# PSPS_AVNC_SRD_sensors-2020-10-12.net
KiCad netlist of a schematic drawn in EAGLE
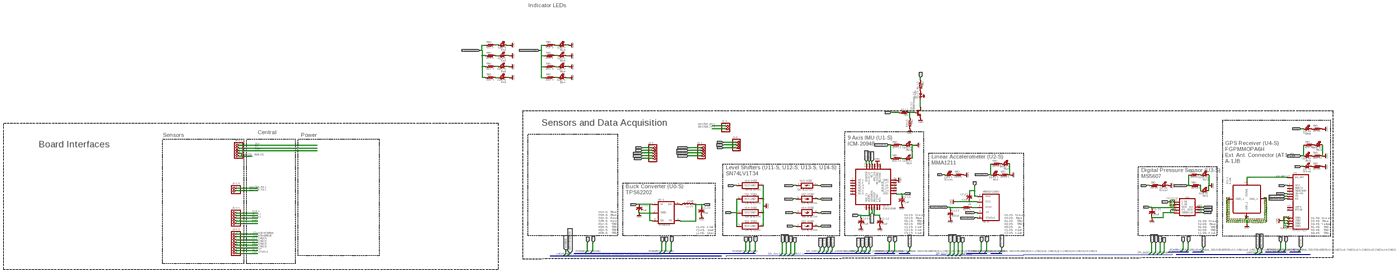
[diagram p0: schematic, sheet 1, overview]
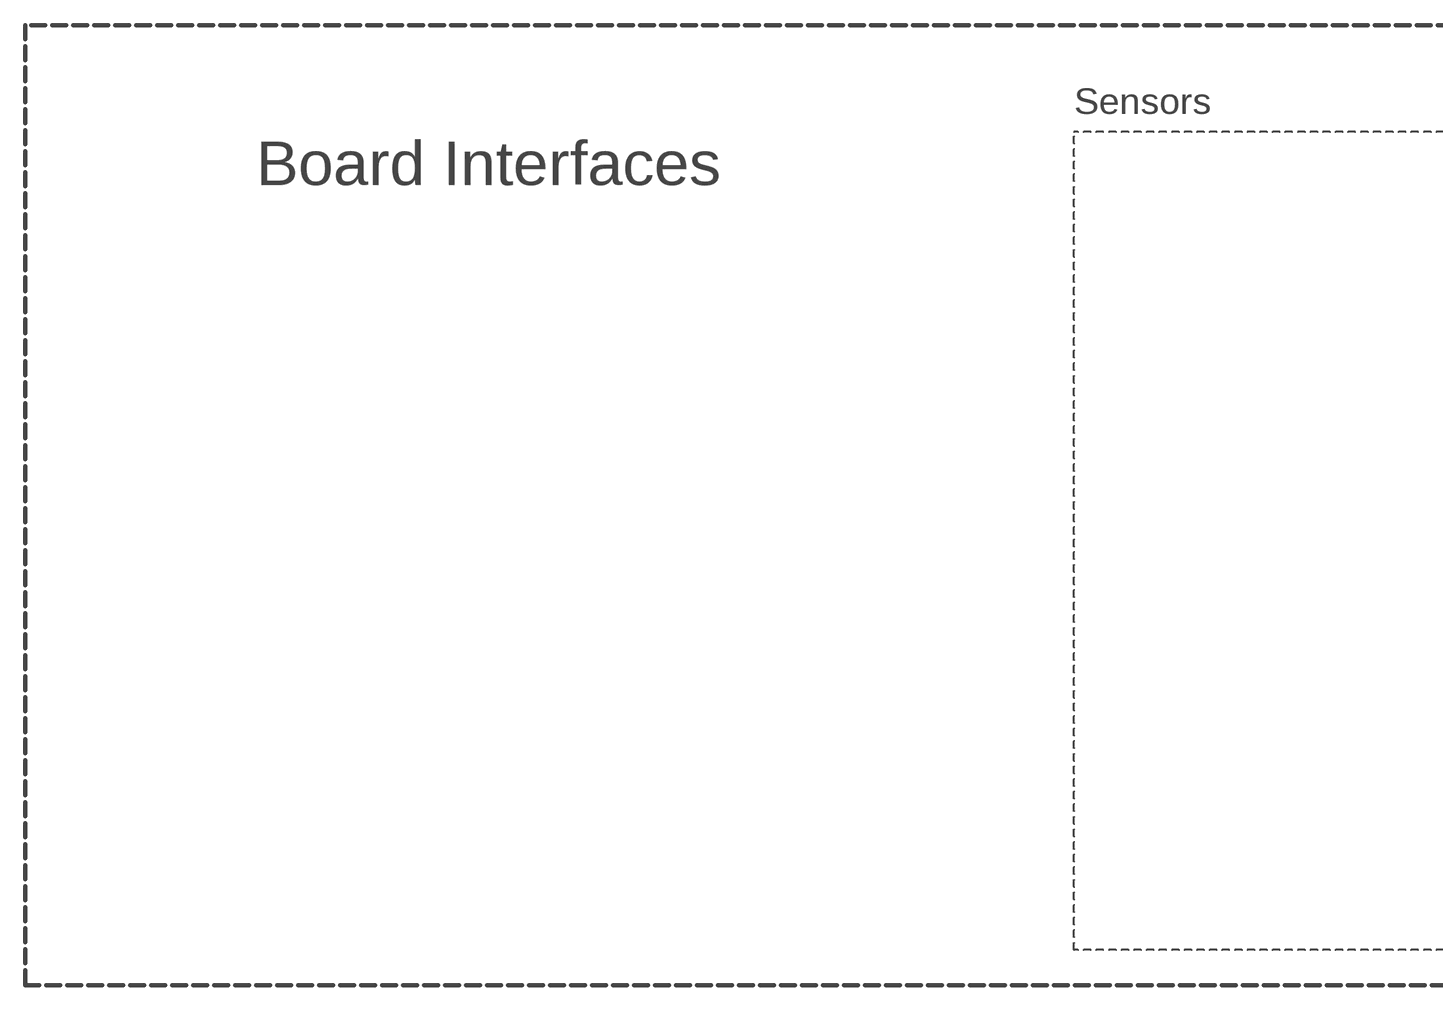
[diagram p1: schematic, sheet 1, part 1 of 4]
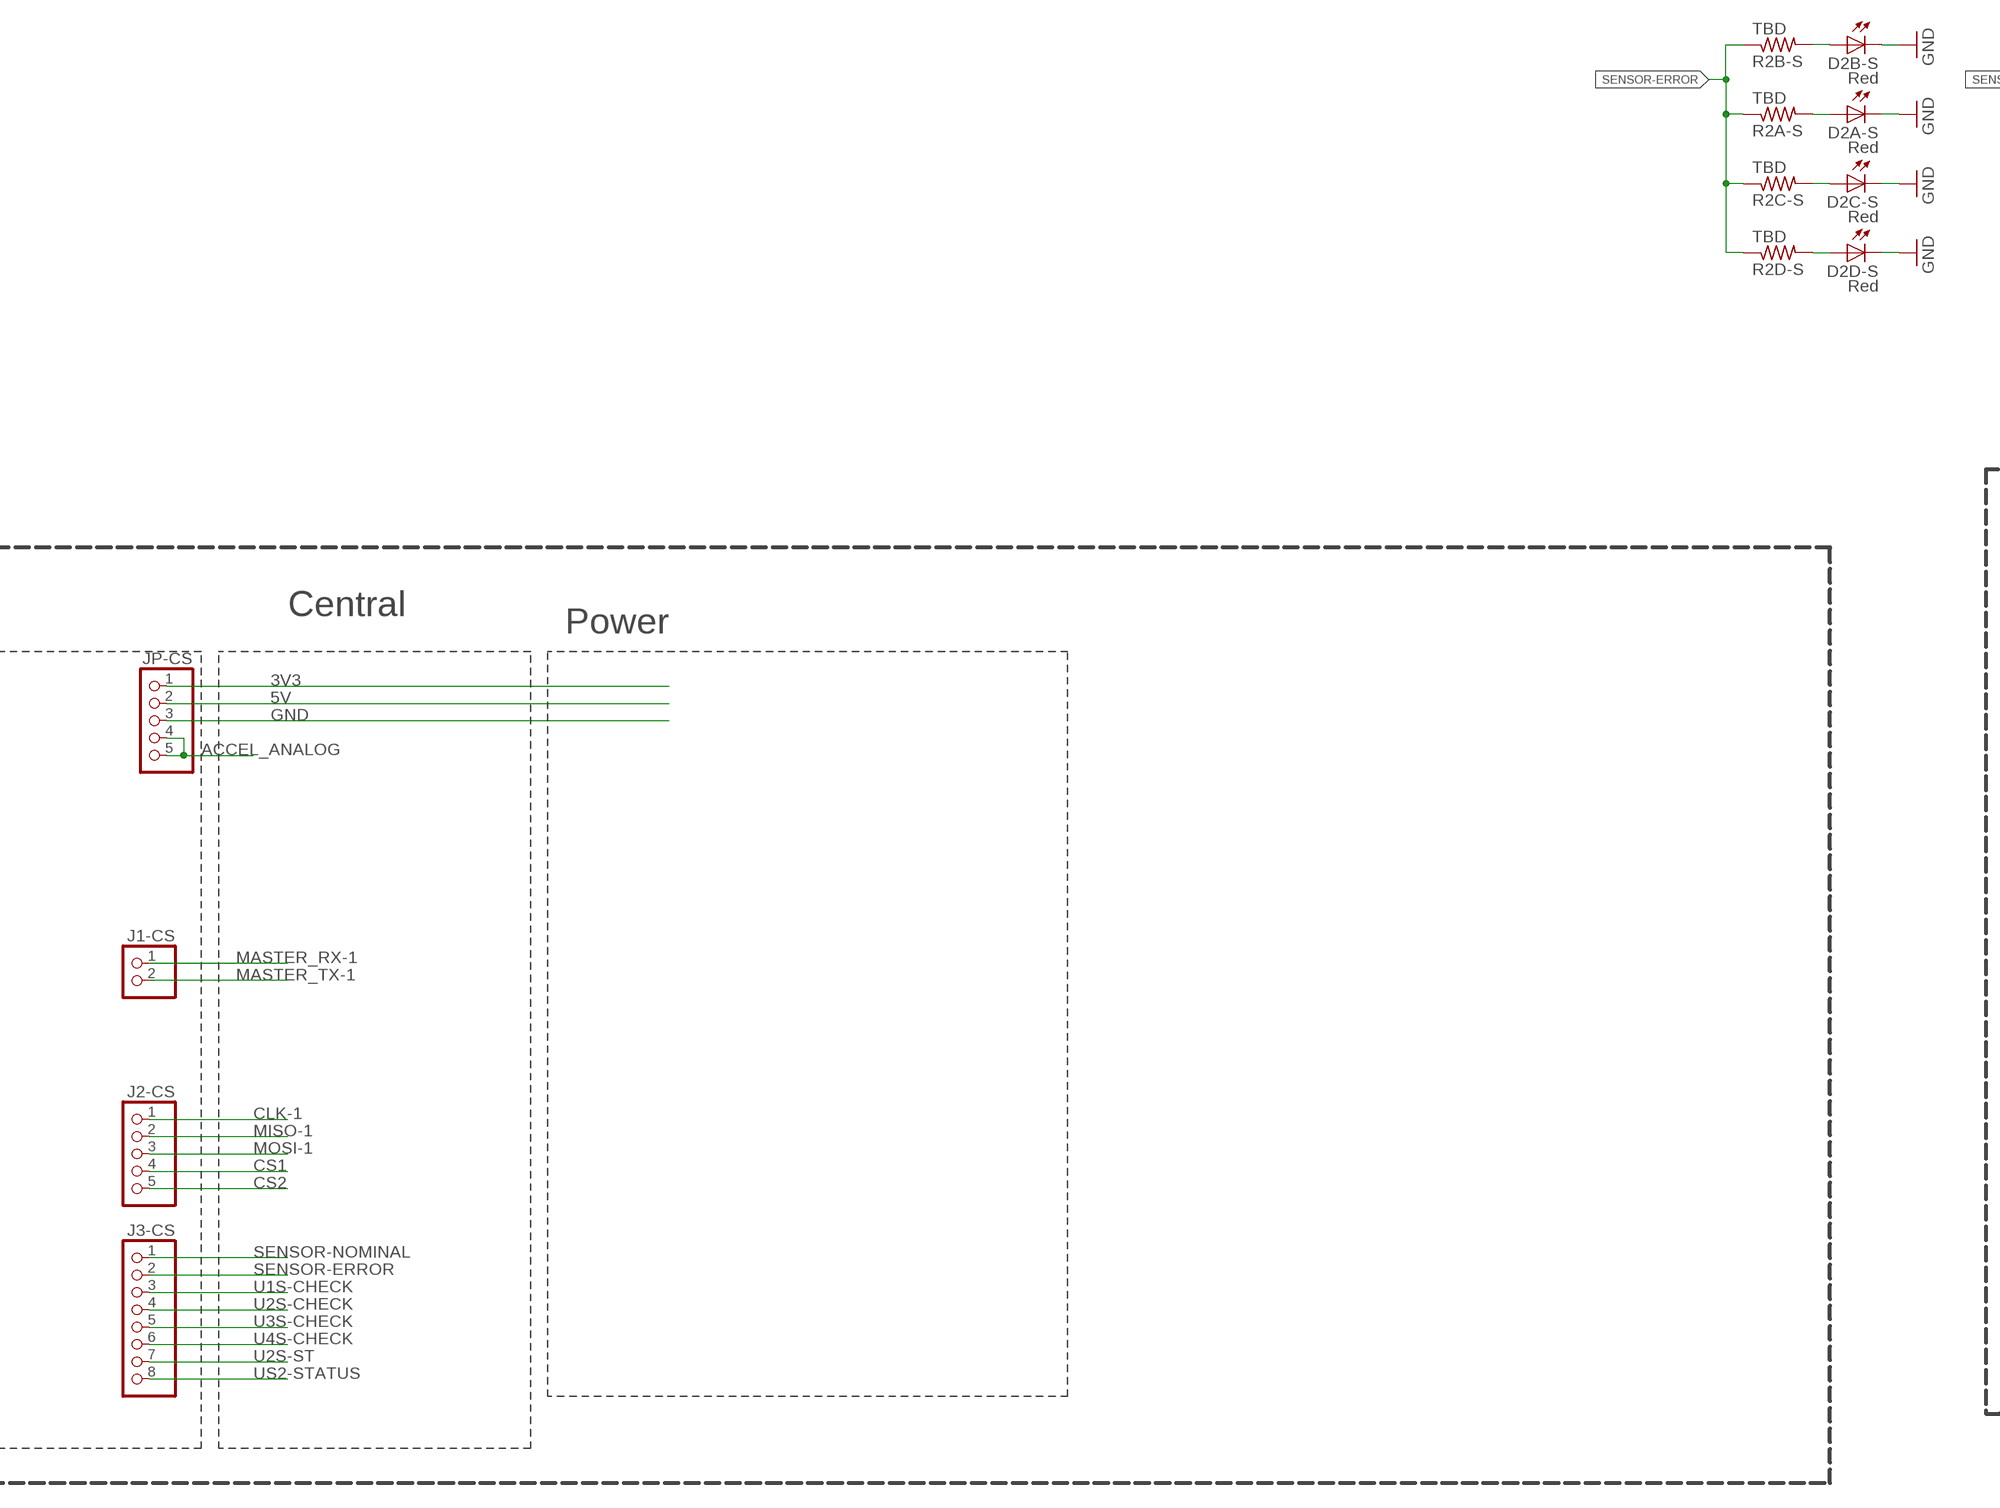
[diagram p2: schematic, sheet 1, part 2 of 4]
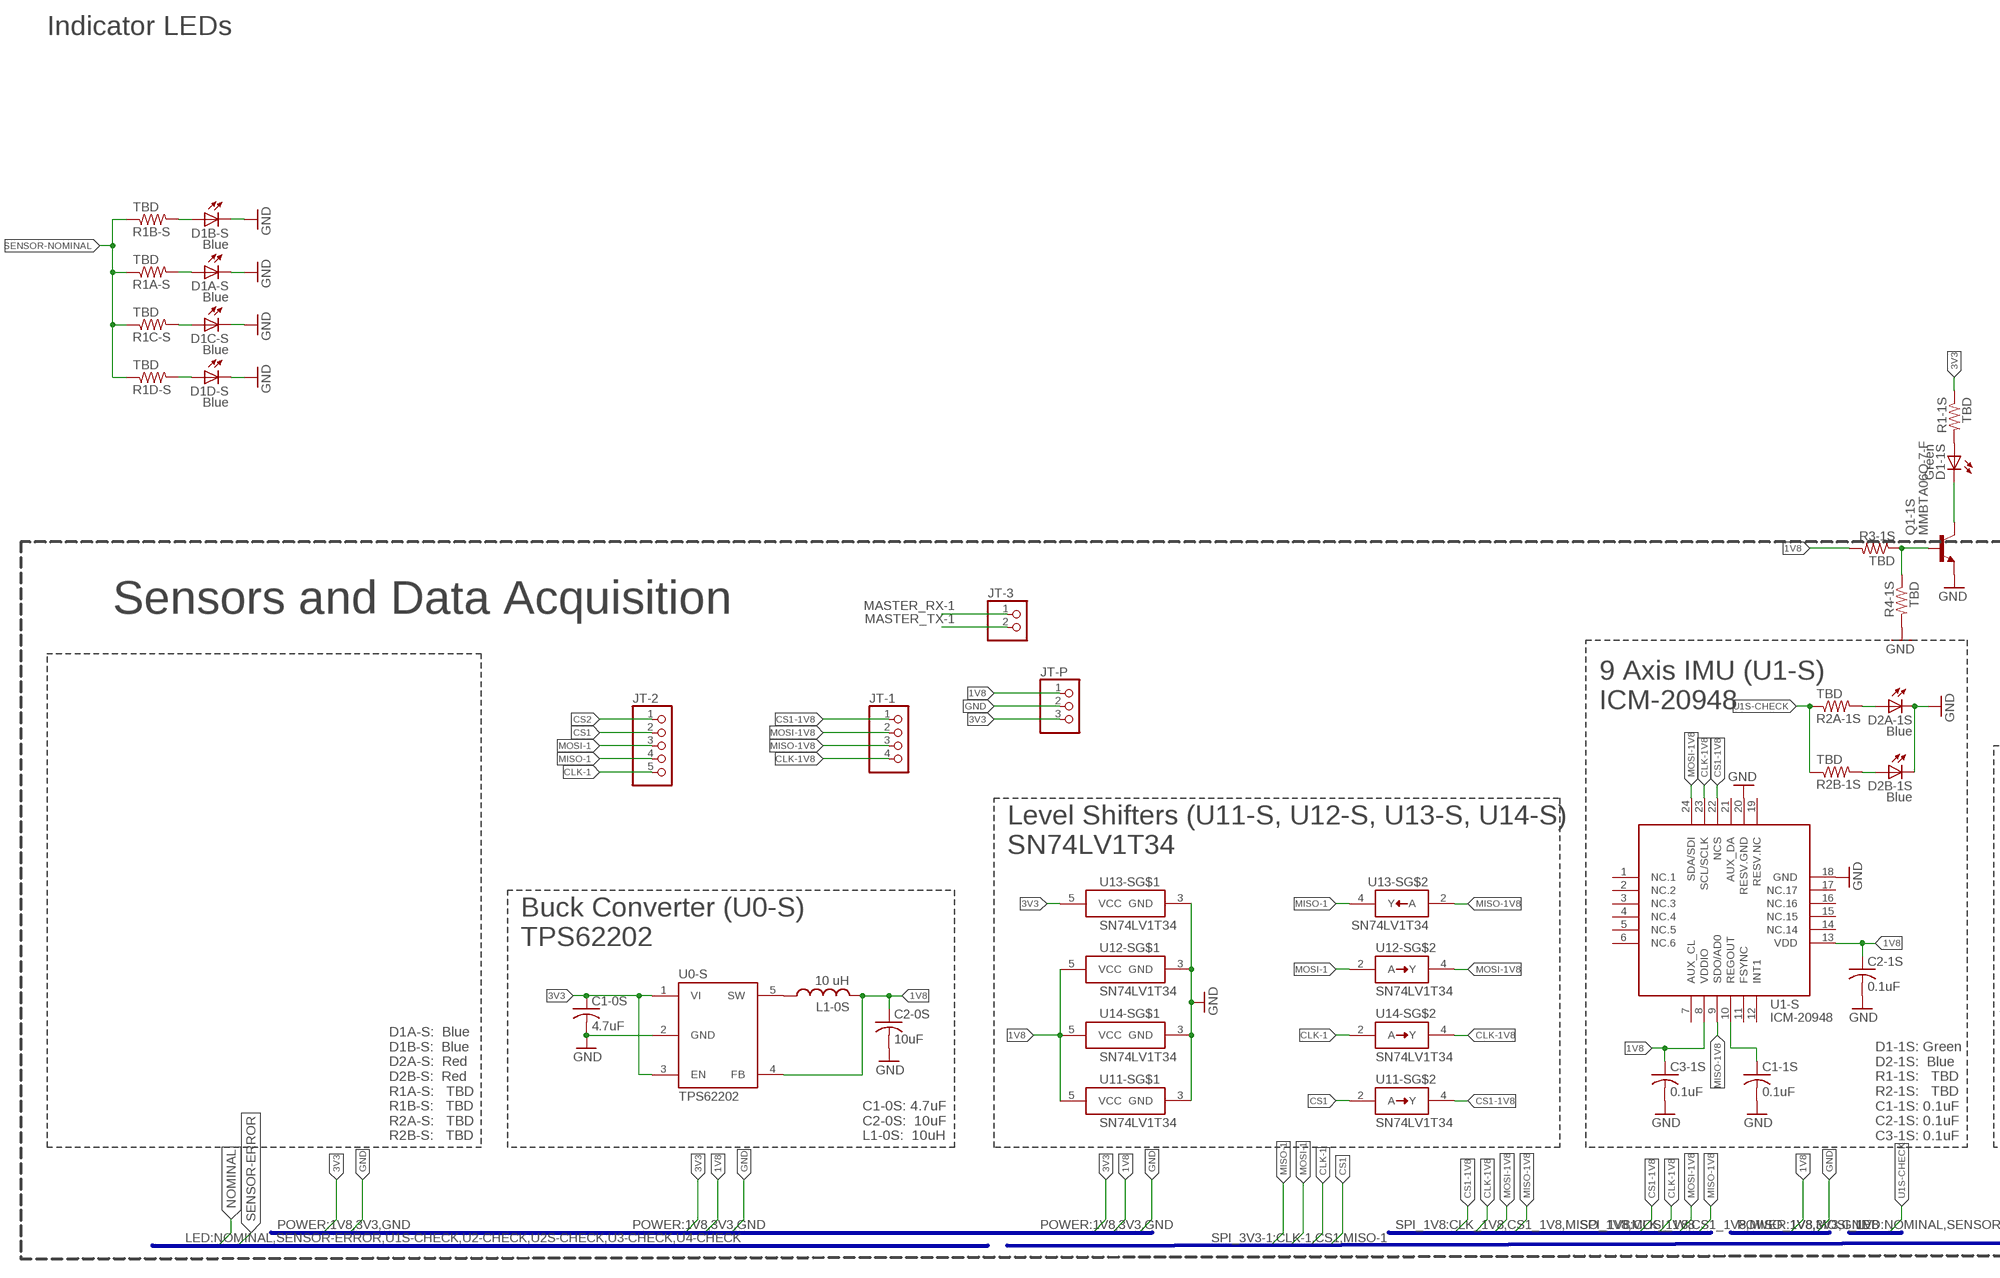
[diagram p3: schematic, sheet 1, part 3 of 4]
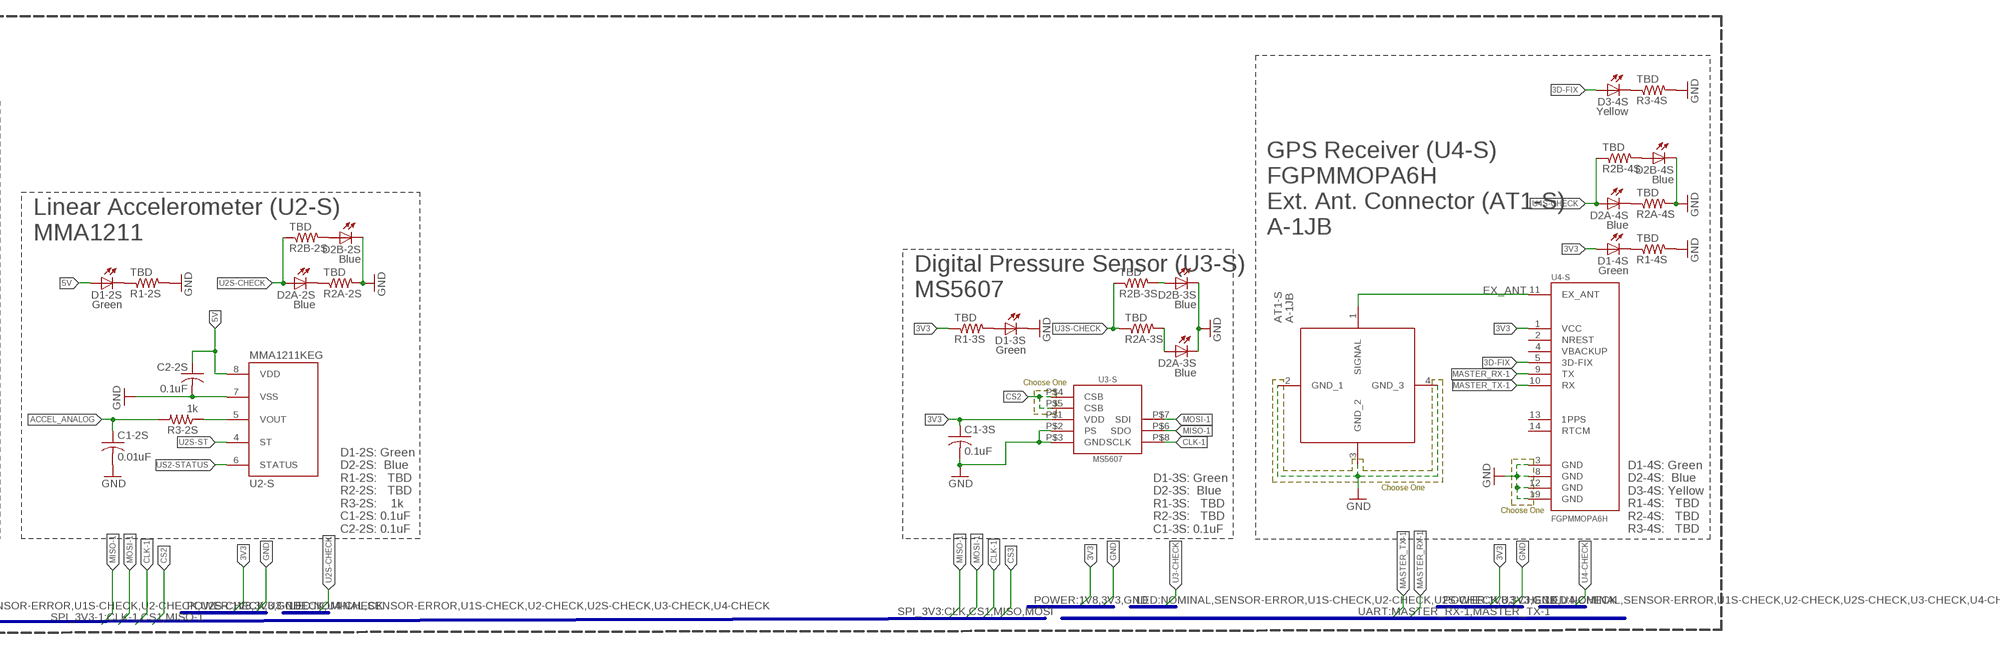
[diagram p4: schematic, sheet 1, part 4 of 4]

(export (version "E")
  (design (tool "Eeschema 10.0.6"))
  (components
    (comp (ref "AT1-S")
      (value "A-1JB")
      (footprint "eagle-import:A1JB")
      (fields (field (name "MOUSER_PART_NUMBER") "523-A-1JB"))
      (libsource (lib "eagle-import") (part "A-1JB"))
    )
    (comp (ref "C1-0S")
      (value "4.7uF")
      (footprint "eagle-import:C0805")
      (libsource (lib "eagle-import") (part "C-USC0805"))
    )
    (comp (ref "C1-1S")
      (value "0.1uF")
      (footprint "eagle-import:C0805")
      (libsource (lib "eagle-import") (part "C-USC0805"))
    )
    (comp (ref "C1-2S")
      (value "0.01uF")
      (footprint "eagle-import:C0805")
      (libsource (lib "eagle-import") (part "C-USC0805"))
    )
    (comp (ref "C1-3S")
      (value "0.1uF")
      (footprint "eagle-import:C0805")
      (libsource (lib "eagle-import") (part "C-USC0805"))
    )
    (comp (ref "C2-0S")
      (value "10uF")
      (footprint "eagle-import:C0805")
      (libsource (lib "eagle-import") (part "C-USC0805"))
    )
    (comp (ref "C2-1S")
      (value "0.1uF")
      (footprint "eagle-import:C0805")
      (libsource (lib "eagle-import") (part "C-USC0805"))
    )
    (comp (ref "C2-2S")
      (value "0.1uF")
      (footprint "eagle-import:C0805")
      (libsource (lib "eagle-import") (part "C-USC0805"))
    )
    (comp (ref "C3-1S")
      (value "0.1uF")
      (footprint "eagle-import:C0805")
      (libsource (lib "eagle-import") (part "C-USC0805"))
    )
    (comp (ref "D1-1S")
      (value "Green")
      (footprint "eagle-import:CHIPLED_0805")
      (libsource (lib "eagle-import") (part "LEDCHIPLED_0805"))
    )
    (comp (ref "D1-2S")
      (value "Green")
      (footprint "eagle-import:CHIPLED_0805")
      (libsource (lib "eagle-import") (part "LEDCHIPLED_0805"))
    )
    (comp (ref "D1-3S")
      (value "Green")
      (footprint "eagle-import:CHIPLED_0805")
      (libsource (lib "eagle-import") (part "LEDCHIPLED_0805"))
    )
    (comp (ref "D1-4S")
      (value "Green")
      (footprint "eagle-import:CHIPLED_0805")
      (libsource (lib "eagle-import") (part "LEDCHIPLED_0805"))
    )
    (comp (ref "D1A-S")
      (value "Blue")
      (footprint "eagle-import:CHIPLED_0805")
      (libsource (lib "eagle-import") (part "LEDCHIPLED_0805"))
    )
    (comp (ref "D1B-S")
      (value "Blue")
      (footprint "eagle-import:CHIPLED_0805")
      (libsource (lib "eagle-import") (part "LEDCHIPLED_0805"))
    )
    (comp (ref "D1C-S")
      (value "Blue")
      (footprint "eagle-import:CHIPLED_0805")
      (libsource (lib "eagle-import") (part "LEDCHIPLED_0805"))
    )
    (comp (ref "D1D-S")
      (value "Blue")
      (footprint "eagle-import:CHIPLED_0805")
      (libsource (lib "eagle-import") (part "LEDCHIPLED_0805"))
    )
    (comp (ref "D2A-1S")
      (value "Blue")
      (footprint "eagle-import:CHIPLED_0805")
      (libsource (lib "eagle-import") (part "LEDCHIPLED_0805"))
    )
    (comp (ref "D2A-2S")
      (value "Blue")
      (footprint "eagle-import:CHIPLED_0805")
      (libsource (lib "eagle-import") (part "LEDCHIPLED_0805"))
    )
    (comp (ref "D2A-3S")
      (value "Blue")
      (footprint "eagle-import:CHIPLED_0805")
      (libsource (lib "eagle-import") (part "LEDCHIPLED_0805"))
    )
    (comp (ref "D2A-4S")
      (value "Blue")
      (footprint "eagle-import:CHIPLED_0805")
      (libsource (lib "eagle-import") (part "LEDCHIPLED_0805"))
    )
    (comp (ref "D2A-S")
      (value "Red")
      (footprint "eagle-import:CHIPLED_0805")
      (libsource (lib "eagle-import") (part "LEDCHIPLED_0805"))
    )
    (comp (ref "D2B-1S")
      (value "Blue")
      (footprint "eagle-import:CHIPLED_0805")
      (libsource (lib "eagle-import") (part "LEDCHIPLED_0805"))
    )
    (comp (ref "D2B-2S")
      (value "Blue")
      (footprint "eagle-import:CHIPLED_0805")
      (libsource (lib "eagle-import") (part "LEDCHIPLED_0805"))
    )
    (comp (ref "D2B-3S")
      (value "Blue")
      (footprint "eagle-import:CHIPLED_0805")
      (libsource (lib "eagle-import") (part "LEDCHIPLED_0805"))
    )
    (comp (ref "D2B-4S")
      (value "Blue")
      (footprint "eagle-import:CHIPLED_0805")
      (libsource (lib "eagle-import") (part "LEDCHIPLED_0805"))
    )
    (comp (ref "D2B-S")
      (value "Red")
      (footprint "eagle-import:CHIPLED_0805")
      (libsource (lib "eagle-import") (part "LEDCHIPLED_0805"))
    )
    (comp (ref "D2C-S")
      (value "Red")
      (footprint "eagle-import:CHIPLED_0805")
      (libsource (lib "eagle-import") (part "LEDCHIPLED_0805"))
    )
    (comp (ref "D2D-S")
      (value "Red")
      (footprint "eagle-import:CHIPLED_0805")
      (libsource (lib "eagle-import") (part "LEDCHIPLED_0805"))
    )
    (comp (ref "D3-4S")
      (value "Yellow")
      (footprint "eagle-import:CHIPLED_0805")
      (libsource (lib "eagle-import") (part "LEDCHIPLED_0805"))
    )
    (comp (ref "J1-CS")
      (value "PINHD-1X2")
      (footprint "eagle-import:1X02")
      (libsource (lib "eagle-import") (part "PINHD-1X2"))
    )
    (comp (ref "J2-CS")
      (value "PINHD-1X5")
      (footprint "eagle-import:1X05")
      (libsource (lib "eagle-import") (part "PINHD-1X5"))
    )
    (comp (ref "J3-CS")
      (value "PINHD-1X8")
      (footprint "eagle-import:1X08")
      (libsource (lib "eagle-import") (part "PINHD-1X8"))
    )
    (comp (ref "JP-CS")
      (value "PINHD-1X5")
      (footprint "eagle-import:1X05")
      (libsource (lib "eagle-import") (part "PINHD-1X5"))
    )
    (comp (ref "JT-1")
      (value "PINHD-1X4")
      (footprint "eagle-import:1X04")
      (libsource (lib "eagle-import") (part "PINHD-1X4"))
    )
    (comp (ref "JT-2")
      (value "PINHD-1X5")
      (footprint "eagle-import:1X05")
      (libsource (lib "eagle-import") (part "PINHD-1X5"))
    )
    (comp (ref "JT-3")
      (value "PINHD-1X2")
      (footprint "eagle-import:1X02")
      (libsource (lib "eagle-import") (part "PINHD-1X2"))
    )
    (comp (ref "JT-P")
      (value "PINHD-1X3")
      (footprint "eagle-import:1X03")
      (libsource (lib "eagle-import") (part "PINHD-1X3"))
    )
    (comp (ref "L1-0S")
      (value "10 uH")
      (footprint "eagle-import:L1812")
      (libsource (lib "eagle-import") (part "L-USL1812"))
    )
    (comp (ref "Q1-1S")
      (value "MMBTA06Q-7-F")
      (footprint "eagle-import:SOT23")
      (libsource (lib "eagle-import") (part "NPN_TRANSISTOR"))
    )
    (comp (ref "R1-1S")
      (value "TBD")
      (footprint "eagle-import:R0805")
      (libsource (lib "eagle-import") (part "R-US_R0805"))
    )
    (comp (ref "R1-2S")
      (value "TBD")
      (footprint "eagle-import:R0805")
      (libsource (lib "eagle-import") (part "R-US_R0805"))
    )
    (comp (ref "R1-3S")
      (value "TBD")
      (footprint "eagle-import:R0805")
      (libsource (lib "eagle-import") (part "R-US_R0805"))
    )
    (comp (ref "R1-4S")
      (value "TBD")
      (footprint "eagle-import:R0805")
      (libsource (lib "eagle-import") (part "R-US_R0805"))
    )
    (comp (ref "R1A-S")
      (value "TBD")
      (footprint "eagle-import:R0805")
      (libsource (lib "eagle-import") (part "R-US_R0805"))
    )
    (comp (ref "R1B-S")
      (value "TBD")
      (footprint "eagle-import:R0805")
      (libsource (lib "eagle-import") (part "R-US_R0805"))
    )
    (comp (ref "R1C-S")
      (value "TBD")
      (footprint "eagle-import:R0805")
      (libsource (lib "eagle-import") (part "R-US_R0805"))
    )
    (comp (ref "R1D-S")
      (value "TBD")
      (footprint "eagle-import:R0805")
      (libsource (lib "eagle-import") (part "R-US_R0805"))
    )
    (comp (ref "R2A-1S")
      (value "TBD")
      (footprint "eagle-import:R0805")
      (libsource (lib "eagle-import") (part "R-US_R0805"))
    )
    (comp (ref "R2A-2S")
      (value "TBD")
      (footprint "eagle-import:R0805")
      (libsource (lib "eagle-import") (part "R-US_R0805"))
    )
    (comp (ref "R2A-3S")
      (value "TBD")
      (footprint "eagle-import:R0805")
      (libsource (lib "eagle-import") (part "R-US_R0805"))
    )
    (comp (ref "R2A-4S")
      (value "TBD")
      (footprint "eagle-import:R0805")
      (libsource (lib "eagle-import") (part "R-US_R0805"))
    )
    (comp (ref "R2A-S")
      (value "TBD")
      (footprint "eagle-import:R0805")
      (libsource (lib "eagle-import") (part "R-US_R0805"))
    )
    (comp (ref "R2B-1S")
      (value "TBD")
      (footprint "eagle-import:R0805")
      (libsource (lib "eagle-import") (part "R-US_R0805"))
    )
    (comp (ref "R2B-2S")
      (value "TBD")
      (footprint "eagle-import:R0805")
      (libsource (lib "eagle-import") (part "R-US_R0805"))
    )
    (comp (ref "R2B-3S")
      (value "TBD")
      (footprint "eagle-import:R0805")
      (libsource (lib "eagle-import") (part "R-US_R0805"))
    )
    (comp (ref "R2B-4S")
      (value "TBD")
      (footprint "eagle-import:R0805")
      (libsource (lib "eagle-import") (part "R-US_R0805"))
    )
    (comp (ref "R2B-S")
      (value "TBD")
      (footprint "eagle-import:R0805")
      (libsource (lib "eagle-import") (part "R-US_R0805"))
    )
    (comp (ref "R2C-S")
      (value "TBD")
      (footprint "eagle-import:R0805")
      (libsource (lib "eagle-import") (part "R-US_R0805"))
    )
    (comp (ref "R2D-S")
      (value "TBD")
      (footprint "eagle-import:R0805")
      (libsource (lib "eagle-import") (part "R-US_R0805"))
    )
    (comp (ref "R3-1S")
      (value "TBD")
      (footprint "eagle-import:R0805")
      (libsource (lib "eagle-import") (part "R-US_R0805"))
    )
    (comp (ref "R3-2S")
      (value "1k")
      (footprint "eagle-import:R0805")
      (libsource (lib "eagle-import") (part "R-US_R0805"))
    )
    (comp (ref "R3-4S")
      (value "TBD")
      (footprint "eagle-import:R0805")
      (libsource (lib "eagle-import") (part "R-US_R0805"))
    )
    (comp (ref "R4-1S")
      (value "TBD")
      (footprint "eagle-import:R0805")
      (libsource (lib "eagle-import") (part "R-US_R0805"))
    )
    (comp (ref "U0-S")
      (value "TPS62202")
      (footprint "eagle-import:SOT95P280X145-5")
      (libsource (lib "eagle-import") (part "TPS62202"))
    )
    (comp (ref "U1-S")
      (value "ICM-20948")
      (footprint "eagle-import:QFN40P300X300X105-25T159X175")
      (libsource (lib "eagle-import") (part "ICM-20948"))
    )
    (comp (ref "U2-S")
      (value "MMA1211KEG")
      (footprint "eagle-import:SOIC127P1041X355-16N")
      (libsource (lib "eagle-import") (part "MMA1211KEG"))
    )
    (comp (ref "U3-S")
      (value "MS5607")
      (footprint "eagle-import:MS5607")
      (libsource (lib "eagle-import") (part "MS5607"))
    )
    (comp (ref "U4-S")
      (value "FGPMMOPA6H")
      (footprint "eagle-import:SOIC127P1800X470-20N")
      (libsource (lib "eagle-import") (part "FGPMMOPA6H"))
    )
    (comp (ref "U11-S")
      (value "SN74LV1T34")
      (footprint "eagle-import:SOT65P210X110-5")
      (libsource (lib "eagle-import") (part "SN74LV1T34"))
    )
    (comp (ref "U12-S")
      (value "SN74LV1T34")
      (footprint "eagle-import:SOT65P210X110-5")
      (libsource (lib "eagle-import") (part "SN74LV1T34"))
    )
    (comp (ref "U13-S")
      (value "SN74LV1T34")
      (footprint "eagle-import:SOT65P210X110-5")
      (libsource (lib "eagle-import") (part "SN74LV1T34"))
    )
    (comp (ref "U14-S")
      (value "SN74LV1T34")
      (footprint "eagle-import:SOT65P210X110-5")
      (libsource (lib "eagle-import") (part "SN74LV1T34"))
    )
  )
  (nets
    (net (code "13") (name "/EX_ANT") (class "Default")
      (node (ref "AT1-S") (pin "1") (pinfunction "SIGNAL_1") (pintype "bidirectional"))
      (node (ref "U4-S") (pin "11") (pinfunction "EX_ANT_11") (pintype "bidirectional"))
    )
    (net (code "20") (name "1V8") (class "Default")
      (node (ref "C2-0S") (pin "1") (pinfunction "1_1") (pintype "passive"))
      (node (ref "C2-1S") (pin "1") (pinfunction "1_1") (pintype "passive"))
      (node (ref "C3-1S") (pin "1") (pinfunction "1_1") (pintype "passive"))
      (node (ref "JT-P") (pin "1") (pinfunction "1_1") (pintype "passive"))
      (node (ref "L1-0S") (pin "2") (pinfunction "2_2") (pintype "passive"))
      (node (ref "R3-1S") (pin "2") (pinfunction "2_2") (pintype "passive"))
      (node (ref "U0-S") (pin "4") (pinfunction "FB_4") (pintype "bidirectional"))
      (node (ref "U1-S") (pin "13") (pinfunction "VDD_13") (pintype "bidirectional"))
      (node (ref "U1-S") (pin "8") (pinfunction "VDDIO_8") (pintype "bidirectional"))
      (node (ref "U11-S") (pin "5") (pinfunction "VCC_5") (pintype "bidirectional"))
      (node (ref "U12-S") (pin "5") (pinfunction "VCC_5") (pintype "bidirectional"))
      (node (ref "U14-S") (pin "5") (pinfunction "VCC_5") (pintype "bidirectional"))
    )
    (net (code "21") (name "3D-FIX") (class "Default")
      (node (ref "D3-4S") (pin "A") (pinfunction "A_A") (pintype "passive"))
      (node (ref "U4-S") (pin "5") (pinfunction "3D-FIX_5") (pintype "bidirectional"))
    )
    (net (code "22") (name "3V3") (class "Default")
      (node (ref "C1-0S") (pin "1") (pinfunction "1_1") (pintype "passive"))
      (node (ref "C1-3S") (pin "1") (pinfunction "1_1") (pintype "passive"))
      (node (ref "D1-4S") (pin "A") (pinfunction "A_A") (pintype "passive"))
      (node (ref "JP-CS") (pin "1") (pinfunction "1_1") (pintype "passive"))
      (node (ref "JT-P") (pin "3") (pinfunction "3_3") (pintype "passive"))
      (node (ref "R1-1S") (pin "1") (pinfunction "1_1") (pintype "passive"))
      (node (ref "R1-3S") (pin "1") (pinfunction "1_1") (pintype "passive"))
      (node (ref "U0-S") (pin "1") (pinfunction "VI_1") (pintype "bidirectional"))
      (node (ref "U0-S") (pin "3") (pinfunction "EN_3") (pintype "bidirectional"))
      (node (ref "U13-S") (pin "5") (pinfunction "VCC_5") (pintype "bidirectional"))
      (node (ref "U3-S") (pin "P$1") (pinfunction "VDD_P$1") (pintype "bidirectional"))
      (node (ref "U4-S") (pin "1") (pinfunction "VCC_1") (pintype "bidirectional"))
    )
    (net (code "23") (name "5V") (class "Default")
      (node (ref "C2-2S") (pin "1") (pinfunction "1_1") (pintype "passive"))
      (node (ref "D1-2S") (pin "A") (pinfunction "A_A") (pintype "passive"))
      (node (ref "JP-CS") (pin "2") (pinfunction "2_2") (pintype "passive"))
      (node (ref "U2-S") (pin "8") (pinfunction "VDD_8") (pintype "bidirectional"))
    )
    (net (code "24") (name "ACCEL_ANALOG") (class "Default")
      (node (ref "C1-2S") (pin "1") (pinfunction "1_1") (pintype "passive"))
      (node (ref "JP-CS") (pin "4") (pinfunction "4_4") (pintype "passive"))
      (node (ref "JP-CS") (pin "5") (pinfunction "5_5") (pintype "passive"))
      (node (ref "R3-2S") (pin "2") (pinfunction "2_2") (pintype "passive"))
    )
    (net (code "25") (name "CLK-1") (class "Default")
      (node (ref "J2-CS") (pin "1") (pinfunction "1_1") (pintype "passive"))
      (node (ref "JT-2") (pin "5") (pinfunction "5_5") (pintype "passive"))
      (node (ref "U14-S") (pin "2") (pinfunction "A_2") (pintype "bidirectional"))
      (node (ref "U3-S") (pin "P$8") (pinfunction "SCLK_P$8") (pintype "bidirectional"))
    )
    (net (code "26") (name "CLK-1V8") (class "Default")
      (node (ref "JT-1") (pin "4") (pinfunction "4_4") (pintype "passive"))
      (node (ref "U1-S") (pin "23") (pinfunction "SCL/SCLK_23") (pintype "bidirectional"))
      (node (ref "U14-S") (pin "4") (pinfunction "Y_4") (pintype "bidirectional"))
    )
    (net (code "27") (name "CS1") (class "Default")
      (node (ref "J2-CS") (pin "4") (pinfunction "4_4") (pintype "passive"))
      (node (ref "JT-2") (pin "2") (pinfunction "2_2") (pintype "passive"))
      (node (ref "U11-S") (pin "2") (pinfunction "A_2") (pintype "bidirectional"))
    )
    (net (code "28") (name "CS1-1V8") (class "Default")
      (node (ref "JT-1") (pin "1") (pinfunction "1_1") (pintype "passive"))
      (node (ref "U1-S") (pin "22") (pinfunction "NCS_22") (pintype "bidirectional"))
      (node (ref "U11-S") (pin "4") (pinfunction "Y_4") (pintype "bidirectional"))
    )
    (net (code "29") (name "CS2") (class "Default")
      (node (ref "J2-CS") (pin "5") (pinfunction "5_5") (pintype "passive"))
      (node (ref "JT-2") (pin "1") (pinfunction "1_1") (pintype "passive"))
      (node (ref "U3-S") (pin "P$4") (pinfunction "CSB_P$4") (pintype "bidirectional"))
      (node (ref "U3-S") (pin "P$5") (pinfunction "CSB_P$5") (pintype "bidirectional"))
    )
    (net (code "31") (name "GND") (class "Default")
      (node (ref "AT1-S") (pin "2") (pinfunction "GND_1_2") (pintype "bidirectional"))
      (node (ref "AT1-S") (pin "3") (pinfunction "GND_2_3") (pintype "bidirectional"))
      (node (ref "AT1-S") (pin "4") (pinfunction "GND_3_4") (pintype "bidirectional"))
      (node (ref "C1-0S") (pin "2") (pinfunction "2_2") (pintype "passive"))
      (node (ref "C1-1S") (pin "2") (pinfunction "2_2") (pintype "passive"))
      (node (ref "C1-2S") (pin "2") (pinfunction "2_2") (pintype "passive"))
      (node (ref "C1-3S") (pin "2") (pinfunction "2_2") (pintype "passive"))
      (node (ref "C2-0S") (pin "2") (pinfunction "2_2") (pintype "passive"))
      (node (ref "C2-1S") (pin "2") (pinfunction "2_2") (pintype "passive"))
      (node (ref "C2-2S") (pin "2") (pinfunction "2_2") (pintype "passive"))
      (node (ref "C3-1S") (pin "2") (pinfunction "2_2") (pintype "passive"))
      (node (ref "D1-3S") (pin "C") (pinfunction "C_C") (pintype "passive"))
      (node (ref "D1A-S") (pin "C") (pinfunction "C_C") (pintype "passive"))
      (node (ref "D1B-S") (pin "C") (pinfunction "C_C") (pintype "passive"))
      (node (ref "D1C-S") (pin "C") (pinfunction "C_C") (pintype "passive"))
      (node (ref "D1D-S") (pin "C") (pinfunction "C_C") (pintype "passive"))
      (node (ref "D2A-1S") (pin "C") (pinfunction "C_C") (pintype "passive"))
      (node (ref "D2A-3S") (pin "C") (pinfunction "C_C") (pintype "passive"))
      (node (ref "D2A-S") (pin "C") (pinfunction "C_C") (pintype "passive"))
      (node (ref "D2B-1S") (pin "C") (pinfunction "C_C") (pintype "passive"))
      (node (ref "D2B-2S") (pin "C") (pinfunction "C_C") (pintype "passive"))
      (node (ref "D2B-3S") (pin "C") (pinfunction "C_C") (pintype "passive"))
      (node (ref "D2B-4S") (pin "C") (pinfunction "C_C") (pintype "passive"))
      (node (ref "D2B-S") (pin "C") (pinfunction "C_C") (pintype "passive"))
      (node (ref "D2C-S") (pin "C") (pinfunction "C_C") (pintype "passive"))
      (node (ref "D2D-S") (pin "C") (pinfunction "C_C") (pintype "passive"))
      (node (ref "JP-CS") (pin "3") (pinfunction "3_3") (pintype "passive"))
      (node (ref "JT-P") (pin "2") (pinfunction "2_2") (pintype "passive"))
      (node (ref "Q1-1S") (pin "3") (pinfunction "E_3") (pintype "passive"))
      (node (ref "R1-2S") (pin "2") (pinfunction "2_2") (pintype "passive"))
      (node (ref "R1-4S") (pin "2") (pinfunction "2_2") (pintype "passive"))
      (node (ref "R2A-2S") (pin "2") (pinfunction "2_2") (pintype "passive"))
      (node (ref "R2A-4S") (pin "2") (pinfunction "2_2") (pintype "passive"))
      (node (ref "R3-4S") (pin "2") (pinfunction "2_2") (pintype "passive"))
      (node (ref "R4-1S") (pin "2") (pinfunction "2_2") (pintype "passive"))
      (node (ref "U0-S") (pin "2") (pinfunction "GND_2") (pintype "bidirectional"))
      (node (ref "U1-S") (pin "18") (pinfunction "GND_18") (pintype "bidirectional"))
      (node (ref "U1-S") (pin "20") (pinfunction "RESV.GND_20") (pintype "bidirectional"))
      (node (ref "U11-S") (pin "3") (pinfunction "GND_3") (pintype "bidirectional"))
      (node (ref "U12-S") (pin "3") (pinfunction "GND_3") (pintype "bidirectional"))
      (node (ref "U13-S") (pin "3") (pinfunction "GND_3") (pintype "bidirectional"))
      (node (ref "U14-S") (pin "3") (pinfunction "GND_3") (pintype "bidirectional"))
      (node (ref "U2-S") (pin "7") (pinfunction "VSS_7") (pintype "bidirectional"))
      (node (ref "U3-S") (pin "P$2") (pinfunction "PS_P$2") (pintype "bidirectional"))
      (node (ref "U3-S") (pin "P$3") (pinfunction "GND_P$3") (pintype "bidirectional"))
      (node (ref "U4-S") (pin "12") (pinfunction "GND_12") (pintype "bidirectional"))
      (node (ref "U4-S") (pin "19") (pinfunction "GND_19") (pintype "bidirectional"))
      (node (ref "U4-S") (pin "3") (pinfunction "GND_3") (pintype "bidirectional"))
      (node (ref "U4-S") (pin "8") (pinfunction "GND_8") (pintype "bidirectional"))
    )
    (net (code "32") (name "MASTER_RX-1") (class "Default")
      (node (ref "J1-CS") (pin "1") (pinfunction "1_1") (pintype "passive"))
      (node (ref "JT-3") (pin "1") (pinfunction "1_1") (pintype "passive"))
      (node (ref "U4-S") (pin "9") (pinfunction "TX_9") (pintype "bidirectional"))
    )
    (net (code "33") (name "MASTER_TX-1") (class "Default")
      (node (ref "J1-CS") (pin "2") (pinfunction "2_2") (pintype "passive"))
      (node (ref "JT-3") (pin "2") (pinfunction "2_2") (pintype "passive"))
      (node (ref "U4-S") (pin "10") (pinfunction "RX_10") (pintype "bidirectional"))
    )
    (net (code "34") (name "MISO-1") (class "Default")
      (node (ref "J2-CS") (pin "2") (pinfunction "2_2") (pintype "passive"))
      (node (ref "JT-2") (pin "4") (pinfunction "4_4") (pintype "passive"))
      (node (ref "U13-S") (pin "4") (pinfunction "Y_4") (pintype "bidirectional"))
      (node (ref "U3-S") (pin "P$6") (pinfunction "SDO_P$6") (pintype "bidirectional"))
    )
    (net (code "35") (name "MISO-1V8") (class "Default")
      (node (ref "JT-1") (pin "3") (pinfunction "3_3") (pintype "passive"))
      (node (ref "U1-S") (pin "9") (pinfunction "SDO/AD0_9") (pintype "bidirectional"))
      (node (ref "U13-S") (pin "2") (pinfunction "A_2") (pintype "bidirectional"))
    )
    (net (code "36") (name "MOSI-1") (class "Default")
      (node (ref "J2-CS") (pin "3") (pinfunction "3_3") (pintype "passive"))
      (node (ref "JT-2") (pin "3") (pinfunction "3_3") (pintype "passive"))
      (node (ref "U12-S") (pin "2") (pinfunction "A_2") (pintype "bidirectional"))
      (node (ref "U3-S") (pin "P$7") (pinfunction "SDI_P$7") (pintype "bidirectional"))
    )
    (net (code "37") (name "MOSI-1V8") (class "Default")
      (node (ref "JT-1") (pin "2") (pinfunction "2_2") (pintype "passive"))
      (node (ref "U1-S") (pin "24") (pinfunction "SDA/SDI_24") (pintype "bidirectional"))
      (node (ref "U12-S") (pin "4") (pinfunction "Y_4") (pintype "bidirectional"))
    )
    (net (code "39") (name "Net-(D1-1S-PadA)") (class "Default")
      (node (ref "D1-1S") (pin "A") (pinfunction "A_A") (pintype "passive"))
      (node (ref "R1-1S") (pin "2") (pinfunction "2_2") (pintype "passive"))
    )
    (net (code "40") (name "Net-(D1-2S-PadC)") (class "Default")
      (node (ref "D1-2S") (pin "C") (pinfunction "C_C") (pintype "passive"))
      (node (ref "R1-2S") (pin "1") (pinfunction "1_1") (pintype "passive"))
    )
    (net (code "41") (name "Net-(D1-3S-PadA)") (class "Default")
      (node (ref "D1-3S") (pin "A") (pinfunction "A_A") (pintype "passive"))
      (node (ref "R1-3S") (pin "2") (pinfunction "2_2") (pintype "passive"))
    )
    (net (code "42") (name "Net-(D1-4S-PadC)") (class "Default")
      (node (ref "D1-4S") (pin "C") (pinfunction "C_C") (pintype "passive"))
      (node (ref "R1-4S") (pin "1") (pinfunction "1_1") (pintype "passive"))
    )
    (net (code "43") (name "Net-(D1A-S-PadA)") (class "Default")
      (node (ref "D1A-S") (pin "A") (pinfunction "A_A") (pintype "passive"))
      (node (ref "R1A-S") (pin "2") (pinfunction "2_2") (pintype "passive"))
    )
    (net (code "44") (name "Net-(D1B-S-PadA)") (class "Default")
      (node (ref "D1B-S") (pin "A") (pinfunction "A_A") (pintype "passive"))
      (node (ref "R1B-S") (pin "2") (pinfunction "2_2") (pintype "passive"))
    )
    (net (code "45") (name "Net-(D1C-S-PadA)") (class "Default")
      (node (ref "D1C-S") (pin "A") (pinfunction "A_A") (pintype "passive"))
      (node (ref "R1C-S") (pin "2") (pinfunction "2_2") (pintype "passive"))
    )
    (net (code "46") (name "Net-(D1D-S-PadA)") (class "Default")
      (node (ref "D1D-S") (pin "A") (pinfunction "A_A") (pintype "passive"))
      (node (ref "R1D-S") (pin "2") (pinfunction "2_2") (pintype "passive"))
    )
    (net (code "47") (name "Net-(D2A-1S-PadA)") (class "Default")
      (node (ref "D2A-1S") (pin "A") (pinfunction "A_A") (pintype "passive"))
      (node (ref "R2A-1S") (pin "2") (pinfunction "2_2") (pintype "passive"))
    )
    (net (code "48") (name "Net-(D2A-2S-PadC)") (class "Default")
      (node (ref "D2A-2S") (pin "C") (pinfunction "C_C") (pintype "passive"))
      (node (ref "R2A-2S") (pin "1") (pinfunction "1_1") (pintype "passive"))
    )
    (net (code "49") (name "Net-(D2A-3S-PadA)") (class "Default")
      (node (ref "D2A-3S") (pin "A") (pinfunction "A_A") (pintype "passive"))
      (node (ref "R2A-3S") (pin "2") (pinfunction "2_2") (pintype "passive"))
    )
    (net (code "50") (name "Net-(D2A-4S-PadC)") (class "Default")
      (node (ref "D2A-4S") (pin "C") (pinfunction "C_C") (pintype "passive"))
      (node (ref "R2A-4S") (pin "1") (pinfunction "1_1") (pintype "passive"))
    )
    (net (code "51") (name "Net-(D2A-S-PadA)") (class "Default")
      (node (ref "D2A-S") (pin "A") (pinfunction "A_A") (pintype "passive"))
      (node (ref "R2A-S") (pin "2") (pinfunction "2_2") (pintype "passive"))
    )
    (net (code "52") (name "Net-(D2B-1S-PadA)") (class "Default")
      (node (ref "D2B-1S") (pin "A") (pinfunction "A_A") (pintype "passive"))
      (node (ref "R2B-1S") (pin "2") (pinfunction "2_2") (pintype "passive"))
    )
    (net (code "53") (name "Net-(D2B-2S-PadA)") (class "Default")
      (node (ref "D2B-2S") (pin "A") (pinfunction "A_A") (pintype "passive"))
      (node (ref "R2B-2S") (pin "2") (pinfunction "2_2") (pintype "passive"))
    )
    (net (code "54") (name "Net-(D2B-3S-PadA)") (class "Default")
      (node (ref "D2B-3S") (pin "A") (pinfunction "A_A") (pintype "passive"))
      (node (ref "R2B-3S") (pin "2") (pinfunction "2_2") (pintype "passive"))
    )
    (net (code "55") (name "Net-(D2B-4S-PadA)") (class "Default")
      (node (ref "D2B-4S") (pin "A") (pinfunction "A_A") (pintype "passive"))
      (node (ref "R2B-4S") (pin "2") (pinfunction "2_2") (pintype "passive"))
    )
    (net (code "56") (name "Net-(D2B-S-PadA)") (class "Default")
      (node (ref "D2B-S") (pin "A") (pinfunction "A_A") (pintype "passive"))
      (node (ref "R2B-S") (pin "2") (pinfunction "2_2") (pintype "passive"))
    )
    (net (code "57") (name "Net-(D2C-S-PadA)") (class "Default")
      (node (ref "D2C-S") (pin "A") (pinfunction "A_A") (pintype "passive"))
      (node (ref "R2C-S") (pin "2") (pinfunction "2_2") (pintype "passive"))
    )
    (net (code "58") (name "Net-(D2D-S-PadA)") (class "Default")
      (node (ref "D2D-S") (pin "A") (pinfunction "A_A") (pintype "passive"))
      (node (ref "R2D-S") (pin "2") (pinfunction "2_2") (pintype "passive"))
    )
    (net (code "59") (name "Net-(D3-4S-PadC)") (class "Default")
      (node (ref "D3-4S") (pin "C") (pinfunction "C_C") (pintype "passive"))
      (node (ref "R3-4S") (pin "1") (pinfunction "1_1") (pintype "passive"))
    )
    (net (code "60") (name "Net-(Q1-1S-B)") (class "Default")
      (node (ref "Q1-1S") (pin "1") (pinfunction "B_1") (pintype "passive"))
      (node (ref "R3-1S") (pin "1") (pinfunction "1_1") (pintype "passive"))
      (node (ref "R4-1S") (pin "1") (pinfunction "1_1") (pintype "passive"))
    )
    (net (code "61") (name "Net-(Q1-1S-C)") (class "Default")
      (node (ref "D1-1S") (pin "C") (pinfunction "C_C") (pintype "passive"))
      (node (ref "Q1-1S") (pin "2") (pinfunction "C_2") (pintype "passive"))
    )
    (net (code "62") (name "Net-(U0-S-SW)") (class "Default")
      (node (ref "L1-0S") (pin "1") (pinfunction "1_1") (pintype "passive"))
      (node (ref "U0-S") (pin "5") (pinfunction "SW_5") (pintype "bidirectional"))
    )
    (net (code "63") (name "Net-(U1-S-REGOUT)") (class "Default")
      (node (ref "C1-1S") (pin "1") (pinfunction "1_1") (pintype "passive"))
      (node (ref "U1-S") (pin "10") (pinfunction "REGOUT_10") (pintype "bidirectional"))
    )
    (net (code "64") (name "Net-(U2-S-VOUT)") (class "Default")
      (node (ref "R3-2S") (pin "1") (pinfunction "1_1") (pintype "passive"))
      (node (ref "U2-S") (pin "5") (pinfunction "VOUT_5") (pintype "bidirectional"))
    )
    (net (code "65") (name "SENSOR-ERROR") (class "Default")
      (node (ref "J3-CS") (pin "2") (pinfunction "2_2") (pintype "passive"))
      (node (ref "R2A-S") (pin "1") (pinfunction "1_1") (pintype "passive"))
      (node (ref "R2B-S") (pin "1") (pinfunction "1_1") (pintype "passive"))
      (node (ref "R2C-S") (pin "1") (pinfunction "1_1") (pintype "passive"))
      (node (ref "R2D-S") (pin "1") (pinfunction "1_1") (pintype "passive"))
    )
    (net (code "66") (name "SENSOR-NOMINAL") (class "Default")
      (node (ref "J3-CS") (pin "1") (pinfunction "1_1") (pintype "passive"))
      (node (ref "R1A-S") (pin "1") (pinfunction "1_1") (pintype "passive"))
      (node (ref "R1B-S") (pin "1") (pinfunction "1_1") (pintype "passive"))
      (node (ref "R1C-S") (pin "1") (pinfunction "1_1") (pintype "passive"))
      (node (ref "R1D-S") (pin "1") (pinfunction "1_1") (pintype "passive"))
    )
    (net (code "67") (name "U1S-CHECK") (class "Default")
      (node (ref "J3-CS") (pin "3") (pinfunction "3_3") (pintype "passive"))
      (node (ref "R2A-1S") (pin "1") (pinfunction "1_1") (pintype "passive"))
      (node (ref "R2B-1S") (pin "1") (pinfunction "1_1") (pintype "passive"))
    )
    (net (code "68") (name "U2S-CHECK") (class "Default")
      (node (ref "D2A-2S") (pin "A") (pinfunction "A_A") (pintype "passive"))
      (node (ref "J3-CS") (pin "4") (pinfunction "4_4") (pintype "passive"))
      (node (ref "R2B-2S") (pin "1") (pinfunction "1_1") (pintype "passive"))
    )
    (net (code "69") (name "U2S-ST") (class "Default")
      (node (ref "J3-CS") (pin "7") (pinfunction "7_7") (pintype "passive"))
      (node (ref "U2-S") (pin "4") (pinfunction "ST_4") (pintype "bidirectional"))
    )
    (net (code "71") (name "U3S-CHECK") (class "Default")
      (node (ref "J3-CS") (pin "5") (pinfunction "5_5") (pintype "passive"))
      (node (ref "R2A-3S") (pin "1") (pinfunction "1_1") (pintype "passive"))
      (node (ref "R2B-3S") (pin "1") (pinfunction "1_1") (pintype "passive"))
    )
    (net (code "73") (name "U4S-CHECK") (class "Default")
      (node (ref "D2A-4S") (pin "A") (pinfunction "A_A") (pintype "passive"))
      (node (ref "J3-CS") (pin "6") (pinfunction "6_6") (pintype "passive"))
      (node (ref "R2B-4S") (pin "1") (pinfunction "1_1") (pintype "passive"))
    )
    (net (code "74") (name "US2-STATUS") (class "Default")
      (node (ref "J3-CS") (pin "8") (pinfunction "8_8") (pintype "passive"))
      (node (ref "U2-S") (pin "6") (pinfunction "STATUS_6") (pintype "bidirectional"))
    )
    (net (code "75") (name "unconnected-(U1-S-AUX_CL-Pad7)") (class "Default")
      (node (ref "U1-S") (pin "7") (pinfunction "AUX_CL_7") (pintype "bidirectional"))
    )
    (net (code "76") (name "unconnected-(U1-S-AUX_DA-Pad21)") (class "Default")
      (node (ref "U1-S") (pin "21") (pinfunction "AUX_DA_21") (pintype "bidirectional"))
    )
    (net (code "77") (name "unconnected-(U1-S-FSYNC-Pad11)") (class "Default")
      (node (ref "U1-S") (pin "11") (pinfunction "FSYNC_11") (pintype "bidirectional"))
    )
    (net (code "78") (name "unconnected-(U1-S-INT1-Pad12)") (class "Default")
      (node (ref "U1-S") (pin "12") (pinfunction "INT1_12") (pintype "bidirectional"))
    )
    (net (code "79") (name "unconnected-(U1-S-NC.1-Pad1)") (class "Default")
      (node (ref "U1-S") (pin "1") (pinfunction "NC.1_1") (pintype "bidirectional"))
    )
    (net (code "80") (name "unconnected-(U1-S-NC.2-Pad2)") (class "Default")
      (node (ref "U1-S") (pin "2") (pinfunction "NC.2_2") (pintype "bidirectional"))
    )
    (net (code "81") (name "unconnected-(U1-S-NC.3-Pad3)") (class "Default")
      (node (ref "U1-S") (pin "3") (pinfunction "NC.3_3") (pintype "bidirectional"))
    )
    (net (code "82") (name "unconnected-(U1-S-NC.4-Pad4)") (class "Default")
      (node (ref "U1-S") (pin "4") (pinfunction "NC.4_4") (pintype "bidirectional"))
    )
    (net (code "83") (name "unconnected-(U1-S-NC.5-Pad5)") (class "Default")
      (node (ref "U1-S") (pin "5") (pinfunction "NC.5_5") (pintype "bidirectional"))
    )
    (net (code "84") (name "unconnected-(U1-S-NC.6-Pad6)") (class "Default")
      (node (ref "U1-S") (pin "6") (pinfunction "NC.6_6") (pintype "bidirectional"))
    )
    (net (code "85") (name "unconnected-(U1-S-NC.14-Pad14)") (class "Default")
      (node (ref "U1-S") (pin "14") (pinfunction "NC.14_14") (pintype "bidirectional"))
    )
    (net (code "86") (name "unconnected-(U1-S-NC.15-Pad15)") (class "Default")
      (node (ref "U1-S") (pin "15") (pinfunction "NC.15_15") (pintype "bidirectional"))
    )
    (net (code "87") (name "unconnected-(U1-S-NC.16-Pad16)") (class "Default")
      (node (ref "U1-S") (pin "16") (pinfunction "NC.16_16") (pintype "bidirectional"))
    )
    (net (code "88") (name "unconnected-(U1-S-NC.17-Pad17)") (class "Default")
      (node (ref "U1-S") (pin "17") (pinfunction "NC.17_17") (pintype "bidirectional"))
    )
    (net (code "89") (name "unconnected-(U1-S-RESV.NC-Pad19)") (class "Default")
      (node (ref "U1-S") (pin "19") (pinfunction "RESV.NC_19") (pintype "bidirectional"))
    )
    (net (code "90") (name "unconnected-(U4-S-1PPS-Pad13)") (class "Default")
      (node (ref "U4-S") (pin "13") (pinfunction "1PPS_13") (pintype "bidirectional"))
    )
    (net (code "91") (name "unconnected-(U4-S-NREST-Pad2)") (class "Default")
      (node (ref "U4-S") (pin "2") (pinfunction "NREST_2") (pintype "bidirectional"))
    )
    (net (code "92") (name "unconnected-(U4-S-RTCM-Pad14)") (class "Default")
      (node (ref "U4-S") (pin "14") (pinfunction "RTCM_14") (pintype "bidirectional"))
    )
    (net (code "93") (name "unconnected-(U4-S-VBACKUP-Pad4)") (class "Default")
      (node (ref "U4-S") (pin "4") (pinfunction "VBACKUP_4") (pintype "bidirectional"))
    )
  )
)
